# FLC100_shield_v2_1.net
KiCad netlist of a schematic drawn in EAGLE
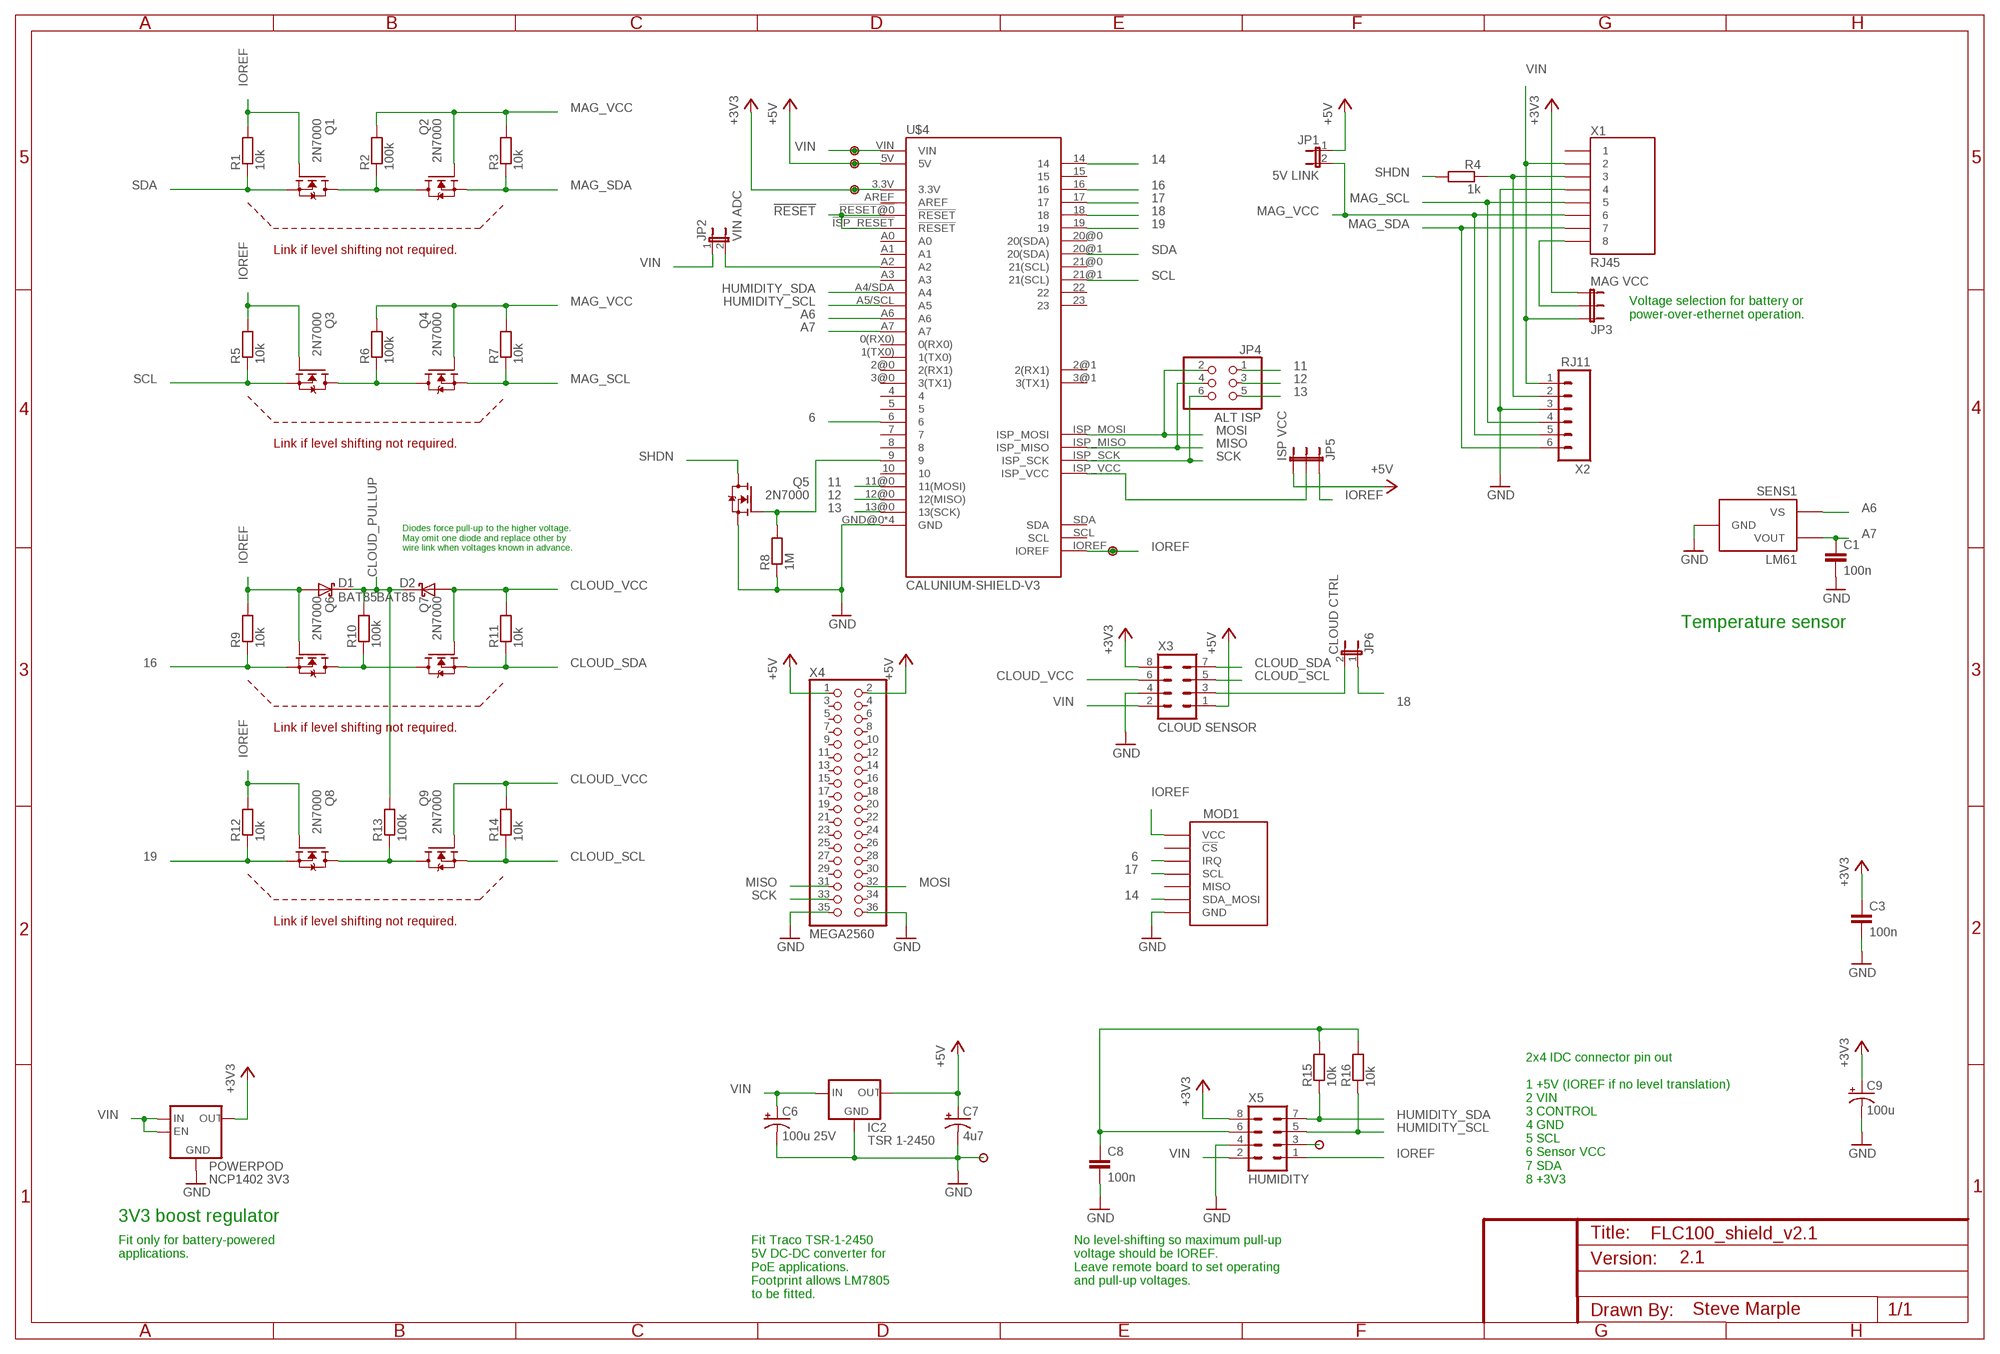
[diagram p0: schematic, sheet 1]

(export (version "E")
  (design (tool "Eeschema 10.0.6"))
  (components
    (comp (ref "C1")
      (value "100n")
      (footprint "eagle-import:CAP-PTH-SMALL")
      (libsource (lib "eagle-import") (part "CAPPTH"))
    )
    (comp (ref "C3")
      (value "100n")
      (footprint "eagle-import:CAP-PTH-SMALL")
      (libsource (lib "eagle-import") (part "CAPPTH"))
    )
    (comp (ref "C6")
      (value "100u 25V")
      (footprint "eagle-import:CPOL-RADIAL-100UF-25V-150MIL")
      (libsource (lib "eagle-import") (part "CAP_POL"))
    )
    (comp (ref "C7")
      (value "4u7")
      (footprint "eagle-import:CPOL-RADIAL-10UF-25V")
      (libsource (lib "eagle-import") (part "CAP_POLPTH2"))
    )
    (comp (ref "C8")
      (value "100n")
      (footprint "eagle-import:CAP-PTH-SMALL")
      (libsource (lib "eagle-import") (part "CAPPTH"))
    )
    (comp (ref "C9")
      (value "100u")
      (footprint "eagle-import:CPOL-RADIAL-10UF-25V")
      (libsource (lib "eagle-import") (part "CAP_POLPTH2"))
    )
    (comp (ref "D1")
      (value "BAT85")
      (footprint "eagle-import:DIODE-TH-0.4")
      (libsource (lib "eagle-import") (part "DIODE-SCHOTTKY"))
    )
    (comp (ref "D2")
      (value "BAT85")
      (footprint "eagle-import:DIODE-TH-0.4")
      (libsource (lib "eagle-import") (part "DIODE-SCHOTTKY"))
    )
    (comp (ref "IC2")
      (value "TSR 1-2450")
      (footprint "eagle-import:78XXL")
      (libsource (lib "eagle-import") (part "V_REG_78XXSIDE"))
    )
    (comp (ref "JP1")
      (value "5V LINK")
      (footprint "eagle-import:1X02")
      (libsource (lib "eagle-import") (part "JUMPER-2PTH"))
    )
    (comp (ref "JP2")
      (value "VIN ADC")
      (footprint "eagle-import:1X02")
      (libsource (lib "eagle-import") (part "JUMPER-2PTH"))
    )
    (comp (ref "JP3")
      (value "MAG VCC")
      (footprint "eagle-import:1X03")
      (libsource (lib "eagle-import") (part "JUMPER-3PTH"))
    )
    (comp (ref "JP4")
      (value "ALT ISP")
      (footprint "eagle-import:2X03")
      (libsource (lib "eagle-import") (part "PINHD-2X3"))
    )
    (comp (ref "JP5")
      (value "ISP VCC")
      (footprint "eagle-import:1X03")
      (libsource (lib "eagle-import") (part "JUMPER-3PTH"))
    )
    (comp (ref "JP6")
      (value "CLOUD CTRL")
      (footprint "eagle-import:1X02")
      (libsource (lib "eagle-import") (part "JUMPER-2PTH"))
    )
    (comp (ref "MOD1")
      (value "EMBEDDED_ADVENTURES_MOD-1016NO-HOLES")
      (footprint "eagle-import:EMBEDDED_ADVENTURES_MOD-1016-NO-HOLES")
      (libsource (lib "eagle-import") (part "EMBEDDED_ADVENTURES_MOD-1016NO-HOLES"))
    )
    (comp (ref "POWERPOD")
      (value "NCP1402 3V3")
      (footprint "eagle-import:CISECO_POWERPOD_NCP1402")
      (libsource (lib "eagle-import") (part "CISECO_POWERPOD_NCP1402"))
    )
    (comp (ref "Q1")
      (value "2N7000")
      (footprint "eagle-import:TO-92")
      (libsource (lib "eagle-import") (part "2N7000"))
    )
    (comp (ref "Q2")
      (value "2N7000")
      (footprint "eagle-import:TO-92")
      (libsource (lib "eagle-import") (part "2N7000"))
    )
    (comp (ref "Q3")
      (value "2N7000")
      (footprint "eagle-import:TO-92")
      (libsource (lib "eagle-import") (part "2N7000"))
    )
    (comp (ref "Q4")
      (value "2N7000")
      (footprint "eagle-import:TO-92")
      (libsource (lib "eagle-import") (part "2N7000"))
    )
    (comp (ref "Q5")
      (value "2N7000")
      (footprint "eagle-import:TO-92")
      (libsource (lib "eagle-import") (part "2N7000"))
    )
    (comp (ref "Q6")
      (value "2N7000")
      (footprint "eagle-import:TO-92")
      (libsource (lib "eagle-import") (part "2N7000"))
    )
    (comp (ref "Q7")
      (value "2N7000")
      (footprint "eagle-import:TO-92")
      (libsource (lib "eagle-import") (part "2N7000"))
    )
    (comp (ref "Q8")
      (value "2N7000")
      (footprint "eagle-import:TO-92")
      (libsource (lib "eagle-import") (part "2N7000"))
    )
    (comp (ref "Q9")
      (value "2N7000")
      (footprint "eagle-import:TO-92")
      (libsource (lib "eagle-import") (part "2N7000"))
    )
    (comp (ref "R1")
      (value "10k")
      (footprint "eagle-import:RES-AXIAL-0.4")
      (libsource (lib "eagle-import") (part "RESISTOR"))
    )
    (comp (ref "R2")
      (value "100k")
      (footprint "eagle-import:RES-AXIAL-0.4")
      (libsource (lib "eagle-import") (part "RESISTOR"))
    )
    (comp (ref "R3")
      (value "10k")
      (footprint "eagle-import:RES-AXIAL-0.4")
      (libsource (lib "eagle-import") (part "RESISTOR"))
    )
    (comp (ref "R4")
      (value "1k")
      (footprint "eagle-import:RES-AXIAL-0.4")
      (libsource (lib "eagle-import") (part "RESISTOR"))
    )
    (comp (ref "R5")
      (value "10k")
      (footprint "eagle-import:RES-AXIAL-0.4")
      (libsource (lib "eagle-import") (part "RESISTOR"))
    )
    (comp (ref "R6")
      (value "100k")
      (footprint "eagle-import:RES-AXIAL-0.4")
      (libsource (lib "eagle-import") (part "RESISTOR"))
    )
    (comp (ref "R7")
      (value "10k")
      (footprint "eagle-import:RES-AXIAL-0.4")
      (libsource (lib "eagle-import") (part "RESISTOR"))
    )
    (comp (ref "R8")
      (value "1M")
      (footprint "eagle-import:RES-AXIAL-0.4")
      (libsource (lib "eagle-import") (part "RESISTOR"))
    )
    (comp (ref "R9")
      (value "10k")
      (footprint "eagle-import:RES-AXIAL-0.4")
      (libsource (lib "eagle-import") (part "RESISTOR"))
    )
    (comp (ref "R10")
      (value "100k")
      (footprint "eagle-import:RES-AXIAL-0.4")
      (libsource (lib "eagle-import") (part "RESISTOR"))
    )
    (comp (ref "R11")
      (value "10k")
      (footprint "eagle-import:RES-AXIAL-0.4")
      (libsource (lib "eagle-import") (part "RESISTOR"))
    )
    (comp (ref "R12")
      (value "10k")
      (footprint "eagle-import:RES-AXIAL-0.4")
      (libsource (lib "eagle-import") (part "RESISTOR"))
    )
    (comp (ref "R13")
      (value "100k")
      (footprint "eagle-import:RES-AXIAL-0.4")
      (libsource (lib "eagle-import") (part "RESISTOR"))
    )
    (comp (ref "R14")
      (value "10k")
      (footprint "eagle-import:RES-AXIAL-0.4")
      (libsource (lib "eagle-import") (part "RESISTOR"))
    )
    (comp (ref "R15")
      (value "10k")
      (footprint "eagle-import:RES-AXIAL-0.4")
      (libsource (lib "eagle-import") (part "RESISTOR"))
    )
    (comp (ref "R16")
      (value "10k")
      (footprint "eagle-import:RES-AXIAL-0.4")
      (libsource (lib "eagle-import") (part "RESISTOR"))
    )
    (comp (ref "SENS1")
      (value "LM61")
      (footprint "eagle-import:TO-92")
      (libsource (lib "eagle-import") (part "LM61"))
    )
    (comp (ref "U$1")
      (value "PAD")
      (footprint "eagle-import:PAD")
      (libsource (lib "eagle-import") (part "PAD"))
    )
    (comp (ref "U$2")
      (value "PAD")
      (footprint "eagle-import:PAD")
      (libsource (lib "eagle-import") (part "PAD"))
    )
    (comp (ref "U$3")
      (value "PAD")
      (footprint "eagle-import:PAD")
      (libsource (lib "eagle-import") (part "PAD"))
    )
    (comp (ref "U$4")
      (value "CALUNIUM-SHIELD-V3")
      (footprint "eagle-import:CALUNIUM-SHIELD-NO-OUTLINE-NO-HOLES-NO-TEXT-V3")
      (libsource (lib "eagle-import") (part "CALUNIUM-SHIELD-V3V3-NO-HOLES-NO-TEXT"))
    )
    (comp (ref "U$5")
      (value "PAD")
      (footprint "eagle-import:PAD")
      (libsource (lib "eagle-import") (part "PAD"))
    )
    (comp (ref "U$13")
      (value "PAD")
      (footprint "eagle-import:PAD")
      (libsource (lib "eagle-import") (part "PAD"))
    )
    (comp (ref "U$14")
      (value "PAD")
      (footprint "eagle-import:PAD")
      (libsource (lib "eagle-import") (part "PAD"))
    )
    (comp (ref "X1")
      (value "RJ45")
      (footprint "eagle-import:RJ45-8")
      (libsource (lib "eagle-import") (part "RJ45-8PTH"))
    )
    (comp (ref "X2")
      (value "RJ11")
      (footprint "eagle-import:RJ11-6")
      (libsource (lib "eagle-import") (part "RJ11-6PTH"))
    )
    (comp (ref "X3")
      (value "CLOUD SENSOR")
      (footprint "eagle-import:ML8")
      (libsource (lib "eagle-import") (part "ML8"))
    )
    (comp (ref "X4")
      (value "MEGA2560")
      (footprint "eagle-import:2X18")
      (libsource (lib "eagle-import") (part "PINHD-2X18"))
    )
    (comp (ref "X5")
      (value "HUMIDITY")
      (footprint "eagle-import:ML8")
      (libsource (lib "eagle-import") (part "ML8"))
    )
  )
  (nets
    (net (code "1") (name "+3V3") (class "Default")
      (node (ref "C3") (pin "1") (pinfunction "1_1") (pintype "passive"))
      (node (ref "C9") (pin "1") (pinfunction "+_1") (pintype "passive"))
      (node (ref "JP3") (pin "3") (pinfunction "3_3") (pintype "passive"))
      (node (ref "POWERPOD") (pin "VOUT") (pinfunction "OUT_VOUT") (pintype "power_in"))
      (node (ref "U$3") (pin "1") (pinfunction "1_1") (pintype "bidirectional"))
      (node (ref "U$4") (pin "3.3V") (pinfunction "3.3V_3.3V") (pintype "bidirectional"))
      (node (ref "X3") (pin "8") (pinfunction "8_8") (pintype "passive"))
      (node (ref "X5") (pin "8") (pinfunction "8_8") (pintype "passive"))
    )
    (net (code "2") (name "+5V") (class "Default")
      (node (ref "C7") (pin "1") (pinfunction "+_1") (pintype "passive"))
      (node (ref "IC2") (pin "OUT") (pinfunction "OUT_OUT") (pintype "power_in"))
      (node (ref "JP1") (pin "1") (pinfunction "1_1") (pintype "passive"))
      (node (ref "JP5") (pin "3") (pinfunction "3_3") (pintype "passive"))
      (node (ref "U$2") (pin "1") (pinfunction "1_1") (pintype "bidirectional"))
      (node (ref "U$4") (pin "5V") (pinfunction "5V_5V") (pintype "bidirectional"))
      (node (ref "X3") (pin "1") (pinfunction "1_1") (pintype "passive"))
      (node (ref "X4") (pin "1") (pinfunction "1_1") (pintype "passive"))
      (node (ref "X4") (pin "2") (pinfunction "2_2") (pintype "passive"))
    )
    (net (code "3") (name "/6") (class "Default")
      (node (ref "MOD1") (pin "IRQ") (pinfunction "IRQ_IRQ") (pintype "bidirectional"))
      (node (ref "U$4") (pin "6") (pinfunction "6_6") (pintype "bidirectional"))
    )
    (net (code "4") (name "/11") (class "Default")
      (node (ref "JP4") (pin "1") (pinfunction "1_1") (pintype "passive"))
      (node (ref "U$4") (pin "11@0") (pinfunction "11(MOSI)_11@0") (pintype "bidirectional"))
    )
    (net (code "5") (name "/12") (class "Default")
      (node (ref "JP4") (pin "3") (pinfunction "3_3") (pintype "passive"))
      (node (ref "U$4") (pin "12@0") (pinfunction "12(MISO)_12@0") (pintype "bidirectional"))
    )
    (net (code "6") (name "/13") (class "Default")
      (node (ref "JP4") (pin "5") (pinfunction "5_5") (pintype "passive"))
      (node (ref "U$4") (pin "13@0") (pinfunction "13(SCK)_13@0") (pintype "bidirectional"))
    )
    (net (code "7") (name "/14") (class "Default")
      (node (ref "MOD1") (pin "SDA_MOSI") (pinfunction "SDA_MOSI_SDA_MOSI") (pintype "bidirectional"))
      (node (ref "U$4") (pin "14") (pinfunction "14_14") (pintype "bidirectional"))
    )
    (net (code "8") (name "/16") (class "Default")
      (node (ref "Q6") (pin "1") (pinfunction "S_1") (pintype "passive"))
      (node (ref "R9") (pin "P$1") (pinfunction "1_P$1") (pintype "passive"))
      (node (ref "U$4") (pin "16") (pinfunction "16_16") (pintype "bidirectional"))
    )
    (net (code "9") (name "/17") (class "Default")
      (node (ref "MOD1") (pin "SCL") (pinfunction "SCL_SCL") (pintype "bidirectional"))
      (node (ref "U$4") (pin "17") (pinfunction "17_17") (pintype "bidirectional"))
    )
    (net (code "10") (name "/18") (class "Default")
      (node (ref "JP6") (pin "1") (pinfunction "1_1") (pintype "passive"))
      (node (ref "U$4") (pin "18") (pinfunction "18_18") (pintype "bidirectional"))
    )
    (net (code "11") (name "/19") (class "Default")
      (node (ref "Q8") (pin "1") (pinfunction "S_1") (pintype "passive"))
      (node (ref "R12") (pin "P$1") (pinfunction "1_P$1") (pintype "passive"))
      (node (ref "U$4") (pin "19") (pinfunction "19_19") (pintype "bidirectional"))
    )
    (net (code "12") (name "/A6") (class "Default")
      (node (ref "SENS1") (pin "1") (pinfunction "VS_1") (pintype "bidirectional"))
      (node (ref "U$4") (pin "A6") (pinfunction "A6_A6") (pintype "bidirectional"))
    )
    (net (code "13") (name "/A7") (class "Default")
      (node (ref "C1") (pin "1") (pinfunction "1_1") (pintype "passive"))
      (node (ref "SENS1") (pin "2") (pinfunction "VOUT_2") (pintype "bidirectional"))
      (node (ref "U$4") (pin "A7") (pinfunction "A7_A7") (pintype "bidirectional"))
    )
    (net (code "14") (name "/CLOUD_PULLUP") (class "Default")
      (node (ref "D1") (pin "C") (pinfunction "C_C") (pintype "passive"))
      (node (ref "D2") (pin "C") (pinfunction "C_C") (pintype "passive"))
      (node (ref "R10") (pin "P$2") (pinfunction "2_P$2") (pintype "passive"))
      (node (ref "R13") (pin "P$2") (pinfunction "2_P$2") (pintype "passive"))
    )
    (net (code "15") (name "/CLOUD_SCL") (class "Default")
      (node (ref "Q9") (pin "1") (pinfunction "S_1") (pintype "passive"))
      (node (ref "R14") (pin "P$1") (pinfunction "1_P$1") (pintype "passive"))
      (node (ref "X3") (pin "5") (pinfunction "5_5") (pintype "passive"))
    )
    (net (code "16") (name "/CLOUD_SDA") (class "Default")
      (node (ref "Q7") (pin "1") (pinfunction "S_1") (pintype "passive"))
      (node (ref "R11") (pin "P$1") (pinfunction "1_P$1") (pintype "passive"))
      (node (ref "X3") (pin "7") (pinfunction "7_7") (pintype "passive"))
    )
    (net (code "17") (name "/CLOUD_VCC") (class "Default")
      (node (ref "D2") (pin "A") (pinfunction "A_A") (pintype "passive"))
      (node (ref "Q7") (pin "2") (pinfunction "G_2") (pintype "passive"))
      (node (ref "Q9") (pin "2") (pinfunction "G_2") (pintype "passive"))
      (node (ref "R11") (pin "P$2") (pinfunction "2_P$2") (pintype "passive"))
      (node (ref "R14") (pin "P$2") (pinfunction "2_P$2") (pintype "passive"))
      (node (ref "X3") (pin "6") (pinfunction "6_6") (pintype "passive"))
    )
    (net (code "18") (name "/HUMIDITY_SCL") (class "Default")
      (node (ref "R16") (pin "P$1") (pinfunction "1_P$1") (pintype "passive"))
      (node (ref "U$4") (pin "A5/SCL") (pinfunction "A5_A5/SCL") (pintype "bidirectional"))
      (node (ref "X5") (pin "5") (pinfunction "5_5") (pintype "passive"))
    )
    (net (code "19") (name "/HUMIDITY_SDA") (class "Default")
      (node (ref "R15") (pin "P$1") (pinfunction "1_P$1") (pintype "passive"))
      (node (ref "U$4") (pin "A4/SDA") (pinfunction "A4_A4/SDA") (pintype "bidirectional"))
      (node (ref "X5") (pin "7") (pinfunction "7_7") (pintype "passive"))
    )
    (net (code "20") (name "/IOREF") (class "Default")
      (node (ref "D1") (pin "A") (pinfunction "A_A") (pintype "passive"))
      (node (ref "JP5") (pin "1") (pinfunction "1_1") (pintype "passive"))
      (node (ref "MOD1") (pin "VCC") (pinfunction "VCC_VCC") (pintype "power_in"))
      (node (ref "Q1") (pin "2") (pinfunction "G_2") (pintype "passive"))
      (node (ref "Q3") (pin "2") (pinfunction "G_2") (pintype "passive"))
      (node (ref "Q6") (pin "2") (pinfunction "G_2") (pintype "passive"))
      (node (ref "Q8") (pin "2") (pinfunction "G_2") (pintype "passive"))
      (node (ref "R1") (pin "P$2") (pinfunction "2_P$2") (pintype "passive"))
      (node (ref "R12") (pin "P$2") (pinfunction "2_P$2") (pintype "passive"))
      (node (ref "R5") (pin "P$2") (pinfunction "2_P$2") (pintype "passive"))
      (node (ref "R9") (pin "P$2") (pinfunction "2_P$2") (pintype "passive"))
      (node (ref "U$4") (pin "IOREF") (pinfunction "IOREF_IOREF") (pintype "bidirectional"))
      (node (ref "U$5") (pin "1") (pinfunction "1_1") (pintype "bidirectional"))
      (node (ref "X5") (pin "1") (pinfunction "1_1") (pintype "passive"))
    )
    (net (code "21") (name "/MAG_SCL") (class "Default")
      (node (ref "Q4") (pin "1") (pinfunction "S_1") (pintype "passive"))
      (node (ref "R7") (pin "P$1") (pinfunction "1_P$1") (pintype "passive"))
      (node (ref "X1") (pin "5") (pinfunction "5_5") (pintype "bidirectional"))
      (node (ref "X2") (pin "4") (pinfunction "4_4") (pintype "passive"))
    )
    (net (code "22") (name "/MAG_SDA") (class "Default")
      (node (ref "Q2") (pin "1") (pinfunction "S_1") (pintype "passive"))
      (node (ref "R3") (pin "P$1") (pinfunction "1_P$1") (pintype "passive"))
      (node (ref "X1") (pin "7") (pinfunction "7_7") (pintype "bidirectional"))
      (node (ref "X2") (pin "6") (pinfunction "6_6") (pintype "passive"))
    )
    (net (code "23") (name "/MAG_VCC") (class "Default")
      (node (ref "JP1") (pin "2") (pinfunction "2_2") (pintype "passive"))
      (node (ref "Q2") (pin "2") (pinfunction "G_2") (pintype "passive"))
      (node (ref "Q4") (pin "2") (pinfunction "G_2") (pintype "passive"))
      (node (ref "R2") (pin "P$2") (pinfunction "2_P$2") (pintype "passive"))
      (node (ref "R3") (pin "P$2") (pinfunction "2_P$2") (pintype "passive"))
      (node (ref "R6") (pin "P$2") (pinfunction "2_P$2") (pintype "passive"))
      (node (ref "R7") (pin "P$2") (pinfunction "2_P$2") (pintype "passive"))
      (node (ref "X1") (pin "6") (pinfunction "6_6") (pintype "bidirectional"))
      (node (ref "X2") (pin "5") (pinfunction "5_5") (pintype "passive"))
    )
    (net (code "24") (name "/MISO") (class "Default")
      (node (ref "JP4") (pin "4") (pinfunction "4_4") (pintype "passive"))
      (node (ref "U$4") (pin "ISP_MISO") (pinfunction "ISP_MISO_ISP_MISO") (pintype "bidirectional"))
      (node (ref "X4") (pin "31") (pinfunction "31_31") (pintype "passive"))
    )
    (net (code "25") (name "/MOSI") (class "Default")
      (node (ref "JP4") (pin "2") (pinfunction "2_2") (pintype "passive"))
      (node (ref "U$4") (pin "ISP_MOSI") (pinfunction "ISP_MOSI_ISP_MOSI") (pintype "bidirectional"))
      (node (ref "X4") (pin "32") (pinfunction "32_32") (pintype "passive"))
    )
    (net (code "26") (name "/SCK") (class "Default")
      (node (ref "JP4") (pin "6") (pinfunction "6_6") (pintype "passive"))
      (node (ref "U$4") (pin "ISP_SCK") (pinfunction "ISP_SCK_ISP_SCK") (pintype "bidirectional"))
      (node (ref "X4") (pin "33") (pinfunction "33_33") (pintype "passive"))
    )
    (net (code "27") (name "/SCL") (class "Default")
      (node (ref "Q3") (pin "1") (pinfunction "S_1") (pintype "passive"))
      (node (ref "R5") (pin "P$1") (pinfunction "1_P$1") (pintype "passive"))
      (node (ref "U$4") (pin "21@1") (pinfunction "21(SCL)_21@1") (pintype "bidirectional"))
    )
    (net (code "28") (name "/SDA") (class "Default")
      (node (ref "Q1") (pin "1") (pinfunction "S_1") (pintype "passive"))
      (node (ref "R1") (pin "P$1") (pinfunction "1_P$1") (pintype "passive"))
      (node (ref "U$4") (pin "20@1") (pinfunction "20(SDA)_20@1") (pintype "bidirectional"))
    )
    (net (code "29") (name "/SHDN") (class "Default")
      (node (ref "Q5") (pin "3") (pinfunction "D_3") (pintype "passive"))
      (node (ref "R4") (pin "P$2") (pinfunction "2_P$2") (pintype "passive"))
    )
    (net (code "30") (name "/VIN") (class "Default")
      (node (ref "C6") (pin "1") (pinfunction "+_1") (pintype "passive"))
      (node (ref "IC2") (pin "IN") (pinfunction "IN_IN") (pintype "input"))
      (node (ref "JP2") (pin "1") (pinfunction "1_1") (pintype "passive"))
      (node (ref "JP3") (pin "1") (pinfunction "1_1") (pintype "passive"))
      (node (ref "POWERPOD") (pin "ENABLE") (pinfunction "ENABLE_ENABLE") (pintype "input"))
      (node (ref "POWERPOD") (pin "VIN") (pinfunction "IN_VIN") (pintype "input"))
      (node (ref "U$1") (pin "1") (pinfunction "1_1") (pintype "bidirectional"))
      (node (ref "U$4") (pin "VIN") (pinfunction "VIN_VIN") (pintype "bidirectional"))
      (node (ref "X1") (pin "2") (pinfunction "2_2") (pintype "bidirectional"))
      (node (ref "X2") (pin "1") (pinfunction "1_1") (pintype "passive"))
      (node (ref "X3") (pin "2") (pinfunction "2_2") (pintype "passive"))
      (node (ref "X5") (pin "2") (pinfunction "2_2") (pintype "passive"))
    )
    (net (code "31") (name "/~{RESET}") (class "Default")
      (node (ref "U$4") (pin "!ISP_RESET") (pinfunction "~{RESET}_!ISP_RESET") (pintype "bidirectional"))
      (node (ref "U$4") (pin "!RESET@0") (pinfunction "~{RESET}_!RESET@0") (pintype "bidirectional"))
    )
    (net (code "32") (name "GND") (class "Default")
      (node (ref "C1") (pin "2") (pinfunction "2_2") (pintype "passive"))
      (node (ref "C3") (pin "2") (pinfunction "2_2") (pintype "passive"))
      (node (ref "C6") (pin "2") (pinfunction "-_2") (pintype "passive"))
      (node (ref "C7") (pin "2") (pinfunction "-_2") (pintype "passive"))
      (node (ref "C8") (pin "2") (pinfunction "2_2") (pintype "passive"))
      (node (ref "C9") (pin "2") (pinfunction "-_2") (pintype "passive"))
      (node (ref "IC2") (pin "GND") (pinfunction "GND_GND") (pintype "power_in"))
      (node (ref "MOD1") (pin "GND") (pinfunction "GND_GND") (pintype "power_in"))
      (node (ref "POWERPOD") (pin "GND") (pinfunction "GND_GND") (pintype "power_in"))
      (node (ref "Q5") (pin "1") (pinfunction "S_1") (pintype "passive"))
      (node (ref "R8") (pin "P$1") (pinfunction "1_P$1") (pintype "passive"))
      (node (ref "SENS1") (pin "3") (pinfunction "GND_3") (pintype "bidirectional"))
      (node (ref "U$14") (pin "1") (pinfunction "1_1") (pintype "bidirectional"))
      (node (ref "U$4") (pin "GND@0") (pinfunction "GND_GND@0") (pintype "bidirectional"))
      (node (ref "U$4") (pin "GND@1") (pinfunction "GND_GND@1") (pintype "bidirectional"))
      (node (ref "U$4") (pin "GND@2") (pinfunction "GND_GND@2") (pintype "bidirectional"))
      (node (ref "U$4") (pin "GND@3") (pinfunction "GND_GND@3") (pintype "bidirectional"))
      (node (ref "X1") (pin "4") (pinfunction "4_4") (pintype "bidirectional"))
      (node (ref "X2") (pin "3") (pinfunction "3_3") (pintype "passive"))
      (node (ref "X3") (pin "4") (pinfunction "4_4") (pintype "passive"))
      (node (ref "X4") (pin "35") (pinfunction "35_35") (pintype "passive"))
      (node (ref "X4") (pin "36") (pinfunction "36_36") (pintype "passive"))
      (node (ref "X5") (pin "4") (pinfunction "4_4") (pintype "passive"))
    )
    (net (code "33") (name "Net-(JP2-Pad2)") (class "Default")
      (node (ref "JP2") (pin "2") (pinfunction "2_2") (pintype "passive"))
      (node (ref "U$4") (pin "A2") (pinfunction "A2_A2") (pintype "bidirectional"))
    )
    (net (code "34") (name "Net-(JP3-Pad2)") (class "Default")
      (node (ref "JP3") (pin "2") (pinfunction "2_2") (pintype "passive"))
      (node (ref "X1") (pin "8") (pinfunction "8_8") (pintype "bidirectional"))
    )
    (net (code "35") (name "Net-(JP5-Pad2)") (class "Default")
      (node (ref "JP5") (pin "2") (pinfunction "2_2") (pintype "passive"))
      (node (ref "U$4") (pin "ISP_VCC") (pinfunction "ISP_VCC_ISP_VCC") (pintype "bidirectional"))
    )
    (net (code "36") (name "Net-(JP6-Pad2)") (class "Default")
      (node (ref "JP6") (pin "2") (pinfunction "2_2") (pintype "passive"))
      (node (ref "X3") (pin "3") (pinfunction "3_3") (pintype "passive"))
    )
    (net (code "37") (name "Net-(Q1-D)") (class "Default")
      (node (ref "Q1") (pin "3") (pinfunction "D_3") (pintype "passive"))
      (node (ref "Q2") (pin "3") (pinfunction "D_3") (pintype "passive"))
      (node (ref "R2") (pin "P$1") (pinfunction "1_P$1") (pintype "passive"))
    )
    (net (code "38") (name "Net-(Q3-D)") (class "Default")
      (node (ref "Q3") (pin "3") (pinfunction "D_3") (pintype "passive"))
      (node (ref "Q4") (pin "3") (pinfunction "D_3") (pintype "passive"))
      (node (ref "R6") (pin "P$1") (pinfunction "1_P$1") (pintype "passive"))
    )
    (net (code "39") (name "Net-(Q5-G)") (class "Default")
      (node (ref "Q5") (pin "2") (pinfunction "G_2") (pintype "passive"))
      (node (ref "R8") (pin "P$2") (pinfunction "2_P$2") (pintype "passive"))
      (node (ref "U$4") (pin "9") (pinfunction "9_9") (pintype "bidirectional"))
    )
    (net (code "40") (name "Net-(Q6-D)") (class "Default")
      (node (ref "Q6") (pin "3") (pinfunction "D_3") (pintype "passive"))
      (node (ref "Q7") (pin "3") (pinfunction "D_3") (pintype "passive"))
      (node (ref "R10") (pin "P$1") (pinfunction "1_P$1") (pintype "passive"))
    )
    (net (code "41") (name "Net-(Q8-D)") (class "Default")
      (node (ref "Q8") (pin "3") (pinfunction "D_3") (pintype "passive"))
      (node (ref "Q9") (pin "3") (pinfunction "D_3") (pintype "passive"))
      (node (ref "R13") (pin "P$1") (pinfunction "1_P$1") (pintype "passive"))
    )
    (net (code "42") (name "Net-(R4-1)") (class "Default")
      (node (ref "R4") (pin "P$1") (pinfunction "1_P$1") (pintype "passive"))
      (node (ref "X1") (pin "3") (pinfunction "3_3") (pintype "bidirectional"))
      (node (ref "X2") (pin "2") (pinfunction "2_2") (pintype "passive"))
    )
    (net (code "43") (name "Net-(R15-2)") (class "Default")
      (node (ref "C8") (pin "1") (pinfunction "1_1") (pintype "passive"))
      (node (ref "R15") (pin "P$2") (pinfunction "2_P$2") (pintype "passive"))
      (node (ref "R16") (pin "P$2") (pinfunction "2_P$2") (pintype "passive"))
      (node (ref "X5") (pin "6") (pinfunction "6_6") (pintype "passive"))
    )
    (net (code "44") (name "Net-(U$13-Pad1)") (class "Default")
      (node (ref "U$13") (pin "1") (pinfunction "1_1") (pintype "bidirectional"))
      (node (ref "X5") (pin "3") (pinfunction "3_3") (pintype "passive"))
    )
    (net (code "45") (name "unconnected-(MOD1-PadMISO)") (class "Default")
      (node (ref "MOD1") (pin "MISO") (pinfunction "MISO_MISO") (pintype "bidirectional"))
    )
    (net (code "46") (name "unconnected-(MOD1-~{CS}-Pad!CS)") (class "Default")
      (node (ref "MOD1") (pin "!CS") (pinfunction "~{CS}_!CS") (pintype "bidirectional"))
    )
    (net (code "47") (name "unconnected-(U$4-2(RX1)-Pad2@0)") (class "Default")
      (node (ref "U$4") (pin "2@0") (pinfunction "2(RX1)_2@0") (pintype "bidirectional"))
    )
    (net (code "48") (name "unconnected-(U$4-2(RX1)-Pad2@1)") (class "Default")
      (node (ref "U$4") (pin "2@1") (pinfunction "2(RX1)_2@1") (pintype "bidirectional"))
    )
    (net (code "49") (name "unconnected-(U$4-3(TX1)-Pad3@0)") (class "Default")
      (node (ref "U$4") (pin "3@0") (pinfunction "3(TX1)_3@0") (pintype "bidirectional"))
    )
    (net (code "50") (name "unconnected-(U$4-3(TX1)-Pad3@1)") (class "Default")
      (node (ref "U$4") (pin "3@1") (pinfunction "3(TX1)_3@1") (pintype "bidirectional"))
    )
    (net (code "51") (name "unconnected-(U$4-20(SDA)-Pad20@0)") (class "Default")
      (node (ref "U$4") (pin "20@0") (pinfunction "20(SDA)_20@0") (pintype "bidirectional"))
    )
    (net (code "52") (name "unconnected-(U$4-21(SCL)-Pad21@0)") (class "Default")
      (node (ref "U$4") (pin "21@0") (pinfunction "21(SCL)_21@0") (pintype "bidirectional"))
    )
    (net (code "53") (name "unconnected-(U$4-Pad0(RX0))") (class "Default")
      (node (ref "U$4") (pin "0(RX0)") (pinfunction "0(RX0)_0(RX0)") (pintype "bidirectional"))
    )
    (net (code "54") (name "unconnected-(U$4-Pad1(TX0))") (class "Default")
      (node (ref "U$4") (pin "1(TX0)") (pinfunction "1(TX0)_1(TX0)") (pintype "bidirectional"))
    )
    (net (code "55") (name "unconnected-(U$4-Pad4)") (class "Default")
      (node (ref "U$4") (pin "4") (pinfunction "4_4") (pintype "bidirectional"))
    )
    (net (code "56") (name "unconnected-(U$4-Pad5)") (class "Default")
      (node (ref "U$4") (pin "5") (pinfunction "5_5") (pintype "bidirectional"))
    )
    (net (code "57") (name "unconnected-(U$4-Pad7)") (class "Default")
      (node (ref "U$4") (pin "7") (pinfunction "7_7") (pintype "bidirectional"))
    )
    (net (code "58") (name "unconnected-(U$4-Pad8)") (class "Default")
      (node (ref "U$4") (pin "8") (pinfunction "8_8") (pintype "bidirectional"))
    )
    (net (code "59") (name "unconnected-(U$4-Pad10)") (class "Default")
      (node (ref "U$4") (pin "10") (pinfunction "10_10") (pintype "bidirectional"))
    )
    (net (code "60") (name "unconnected-(U$4-Pad15)") (class "Default")
      (node (ref "U$4") (pin "15") (pinfunction "15_15") (pintype "bidirectional"))
    )
    (net (code "61") (name "unconnected-(U$4-Pad22)") (class "Default")
      (node (ref "U$4") (pin "22") (pinfunction "22_22") (pintype "bidirectional"))
    )
    (net (code "62") (name "unconnected-(U$4-Pad23)") (class "Default")
      (node (ref "U$4") (pin "23") (pinfunction "23_23") (pintype "bidirectional"))
    )
    (net (code "63") (name "unconnected-(U$4-PadA0)") (class "Default")
      (node (ref "U$4") (pin "A0") (pinfunction "A0_A0") (pintype "bidirectional"))
    )
    (net (code "64") (name "unconnected-(U$4-PadA1)") (class "Default")
      (node (ref "U$4") (pin "A1") (pinfunction "A1_A1") (pintype "bidirectional"))
    )
    (net (code "65") (name "unconnected-(U$4-PadA3)") (class "Default")
      (node (ref "U$4") (pin "A3") (pinfunction "A3_A3") (pintype "bidirectional"))
    )
    (net (code "66") (name "unconnected-(U$4-PadAREF)") (class "Default")
      (node (ref "U$4") (pin "AREF") (pinfunction "AREF_AREF") (pintype "bidirectional"))
    )
    (net (code "67") (name "unconnected-(U$4-PadSCL)") (class "Default")
      (node (ref "U$4") (pin "SCL") (pinfunction "SCL_SCL") (pintype "bidirectional"))
    )
    (net (code "68") (name "unconnected-(U$4-PadSDA)") (class "Default")
      (node (ref "U$4") (pin "SDA") (pinfunction "SDA_SDA") (pintype "bidirectional"))
    )
    (net (code "69") (name "unconnected-(X1-Pad1)") (class "Default")
      (node (ref "X1") (pin "1") (pinfunction "1_1") (pintype "bidirectional"))
    )
    (net (code "70") (name "unconnected-(X4-Pad3)") (class "Default")
      (node (ref "X4") (pin "3") (pinfunction "3_3") (pintype "passive"))
    )
    (net (code "71") (name "unconnected-(X4-Pad4)") (class "Default")
      (node (ref "X4") (pin "4") (pinfunction "4_4") (pintype "passive"))
    )
    (net (code "72") (name "unconnected-(X4-Pad5)") (class "Default")
      (node (ref "X4") (pin "5") (pinfunction "5_5") (pintype "passive"))
    )
    (net (code "73") (name "unconnected-(X4-Pad6)") (class "Default")
      (node (ref "X4") (pin "6") (pinfunction "6_6") (pintype "passive"))
    )
    (net (code "74") (name "unconnected-(X4-Pad7)") (class "Default")
      (node (ref "X4") (pin "7") (pinfunction "7_7") (pintype "passive"))
    )
    (net (code "75") (name "unconnected-(X4-Pad8)") (class "Default")
      (node (ref "X4") (pin "8") (pinfunction "8_8") (pintype "passive"))
    )
    (net (code "76") (name "unconnected-(X4-Pad9)") (class "Default")
      (node (ref "X4") (pin "9") (pinfunction "9_9") (pintype "passive"))
    )
    (net (code "77") (name "unconnected-(X4-Pad10)") (class "Default")
      (node (ref "X4") (pin "10") (pinfunction "10_10") (pintype "passive"))
    )
    (net (code "78") (name "unconnected-(X4-Pad11)") (class "Default")
      (node (ref "X4") (pin "11") (pinfunction "11_11") (pintype "passive"))
    )
    (net (code "79") (name "unconnected-(X4-Pad12)") (class "Default")
      (node (ref "X4") (pin "12") (pinfunction "12_12") (pintype "passive"))
    )
    (net (code "80") (name "unconnected-(X4-Pad13)") (class "Default")
      (node (ref "X4") (pin "13") (pinfunction "13_13") (pintype "passive"))
    )
    (net (code "81") (name "unconnected-(X4-Pad14)") (class "Default")
      (node (ref "X4") (pin "14") (pinfunction "14_14") (pintype "passive"))
    )
    (net (code "82") (name "unconnected-(X4-Pad15)") (class "Default")
      (node (ref "X4") (pin "15") (pinfunction "15_15") (pintype "passive"))
    )
    (net (code "83") (name "unconnected-(X4-Pad16)") (class "Default")
      (node (ref "X4") (pin "16") (pinfunction "16_16") (pintype "passive"))
    )
    (net (code "84") (name "unconnected-(X4-Pad17)") (class "Default")
      (node (ref "X4") (pin "17") (pinfunction "17_17") (pintype "passive"))
    )
    (net (code "85") (name "unconnected-(X4-Pad18)") (class "Default")
      (node (ref "X4") (pin "18") (pinfunction "18_18") (pintype "passive"))
    )
    (net (code "86") (name "unconnected-(X4-Pad19)") (class "Default")
      (node (ref "X4") (pin "19") (pinfunction "19_19") (pintype "passive"))
    )
    (net (code "87") (name "unconnected-(X4-Pad20)") (class "Default")
      (node (ref "X4") (pin "20") (pinfunction "20_20") (pintype "passive"))
    )
    (net (code "88") (name "unconnected-(X4-Pad21)") (class "Default")
      (node (ref "X4") (pin "21") (pinfunction "21_21") (pintype "passive"))
    )
    (net (code "89") (name "unconnected-(X4-Pad22)") (class "Default")
      (node (ref "X4") (pin "22") (pinfunction "22_22") (pintype "passive"))
    )
    (net (code "90") (name "unconnected-(X4-Pad23)") (class "Default")
      (node (ref "X4") (pin "23") (pinfunction "23_23") (pintype "passive"))
    )
    (net (code "91") (name "unconnected-(X4-Pad24)") (class "Default")
      (node (ref "X4") (pin "24") (pinfunction "24_24") (pintype "passive"))
    )
    (net (code "92") (name "unconnected-(X4-Pad25)") (class "Default")
      (node (ref "X4") (pin "25") (pinfunction "25_25") (pintype "passive"))
    )
    (net (code "93") (name "unconnected-(X4-Pad26)") (class "Default")
      (node (ref "X4") (pin "26") (pinfunction "26_26") (pintype "passive"))
    )
    (net (code "94") (name "unconnected-(X4-Pad27)") (class "Default")
      (node (ref "X4") (pin "27") (pinfunction "27_27") (pintype "passive"))
    )
    (net (code "95") (name "unconnected-(X4-Pad28)") (class "Default")
      (node (ref "X4") (pin "28") (pinfunction "28_28") (pintype "passive"))
    )
    (net (code "96") (name "unconnected-(X4-Pad29)") (class "Default")
      (node (ref "X4") (pin "29") (pinfunction "29_29") (pintype "passive"))
    )
    (net (code "97") (name "unconnected-(X4-Pad30)") (class "Default")
      (node (ref "X4") (pin "30") (pinfunction "30_30") (pintype "passive"))
    )
    (net (code "98") (name "unconnected-(X4-Pad34)") (class "Default")
      (node (ref "X4") (pin "34") (pinfunction "34_34") (pintype "passive"))
    )
  )
)
